# Mixer-Analog-OPA2134-Rev-K.net
KiCad netlist of a schematic drawn in EAGLE
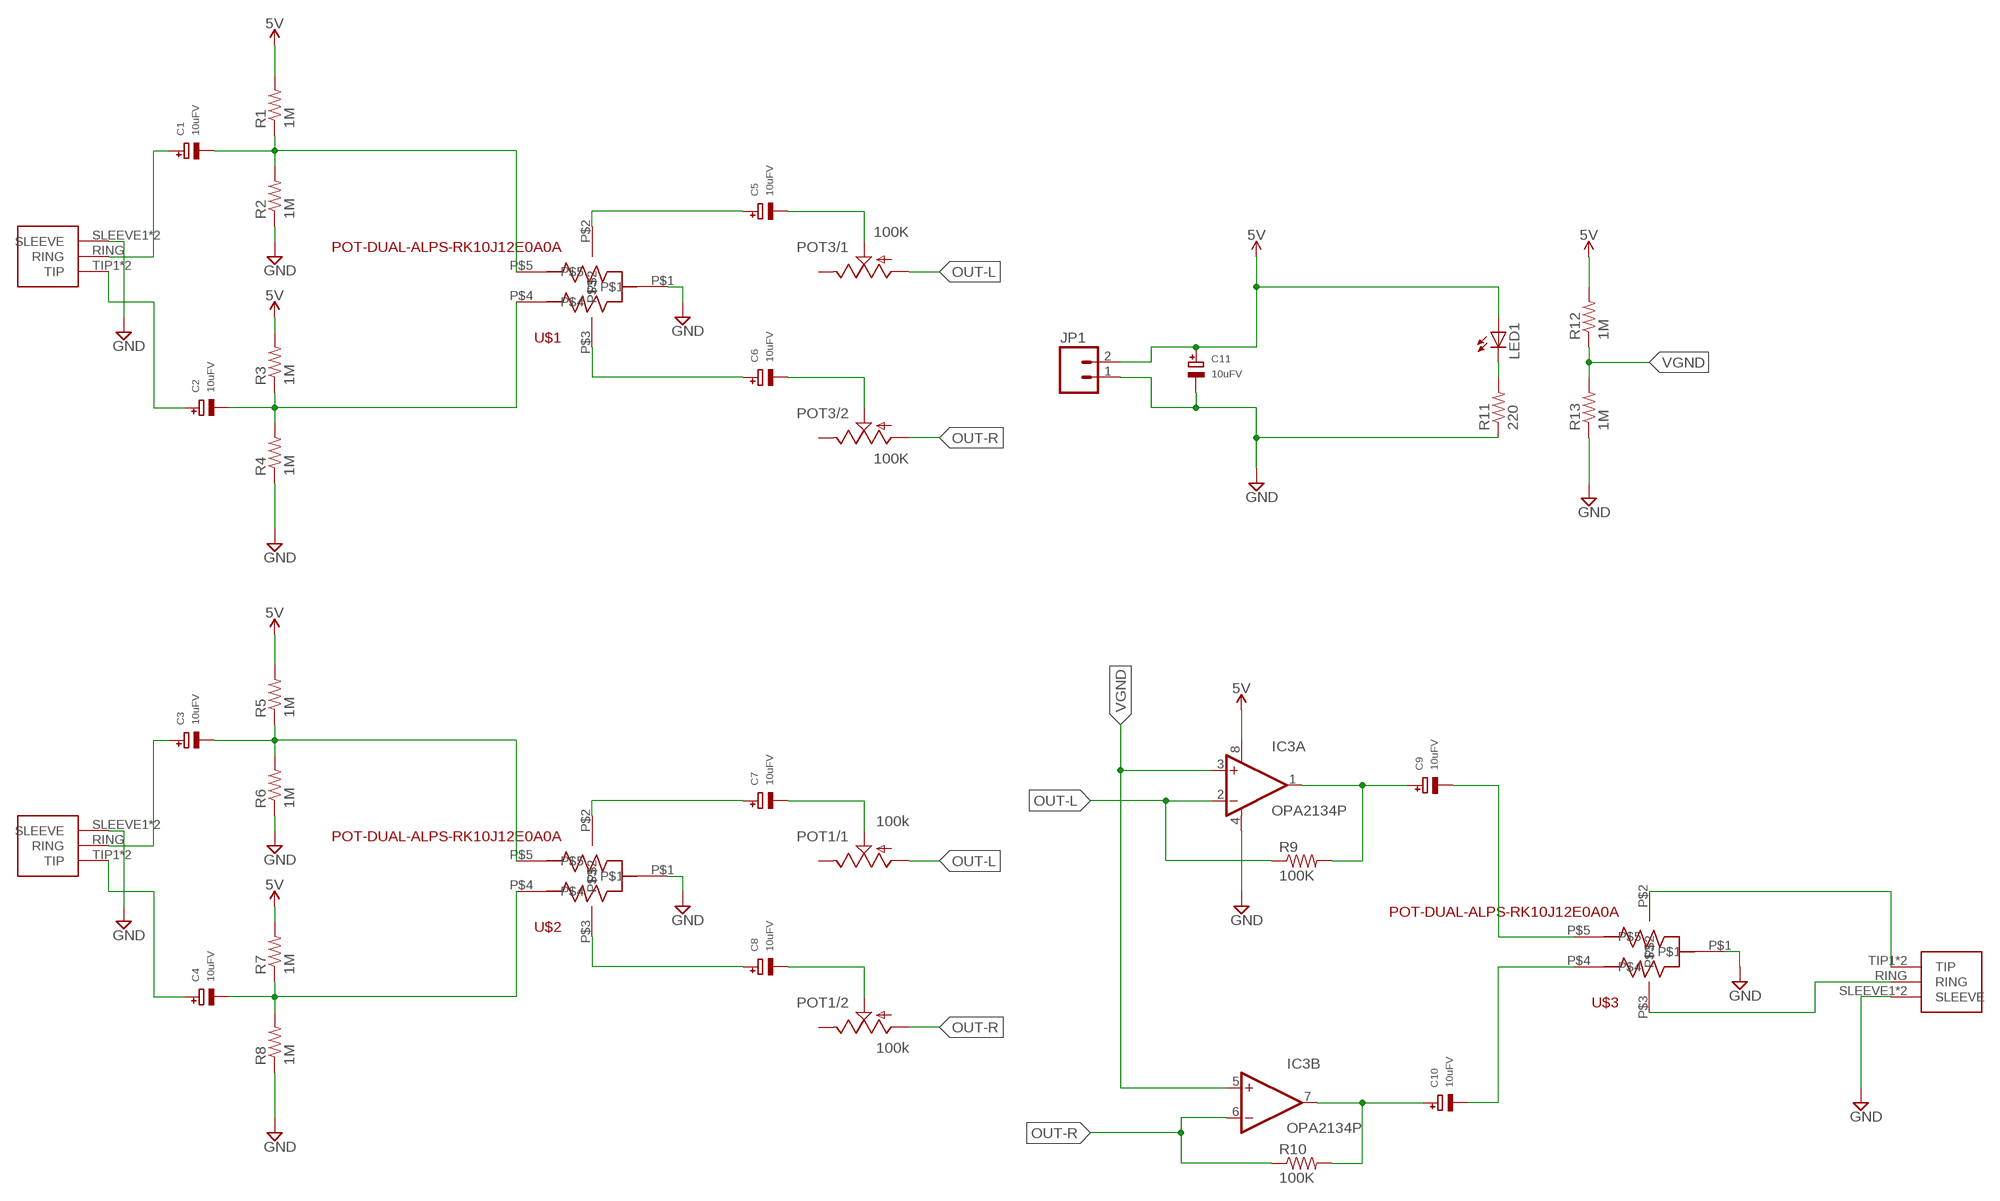
[diagram p0: schematic, sheet 1]

(export (version "E")
  (design (tool "Eeschema 10.0.6"))
  (components
    (comp (ref "C1")
      (value "10uFV")
      (footprint "eagle-import:CELEC_3.5MM_8MM")
      (libsource (lib "eagle-import") (part "CAP_ELECTROLYTICPTH_3.5MMGRID_8MMDIA"))
    )
    (comp (ref "C2")
      (value "10uFV")
      (footprint "eagle-import:CELEC_3.5MM_8MM")
      (libsource (lib "eagle-import") (part "CAP_ELECTROLYTICPTH_3.5MMGRID_8MMDIA"))
    )
    (comp (ref "C3")
      (value "10uFV")
      (footprint "eagle-import:CELEC_3.5MM_8MM")
      (libsource (lib "eagle-import") (part "CAP_ELECTROLYTICPTH_3.5MMGRID_8MMDIA"))
    )
    (comp (ref "C4")
      (value "10uFV")
      (footprint "eagle-import:CELEC_3.5MM_8MM")
      (libsource (lib "eagle-import") (part "CAP_ELECTROLYTICPTH_3.5MMGRID_8MMDIA"))
    )
    (comp (ref "C5")
      (value "10uFV")
      (footprint "eagle-import:CELEC_3.5MM_8MM")
      (libsource (lib "eagle-import") (part "CAP_ELECTROLYTICPTH_3.5MMGRID_8MMDIA"))
    )
    (comp (ref "C6")
      (value "10uFV")
      (footprint "eagle-import:CELEC_3.5MM_8MM")
      (libsource (lib "eagle-import") (part "CAP_ELECTROLYTICPTH_3.5MMGRID_8MMDIA"))
    )
    (comp (ref "C7")
      (value "10uFV")
      (footprint "eagle-import:CELEC_3.5MM_8MM")
      (libsource (lib "eagle-import") (part "CAP_ELECTROLYTICPTH_3.5MMGRID_8MMDIA"))
    )
    (comp (ref "C8")
      (value "10uFV")
      (footprint "eagle-import:CELEC_3.5MM_8MM")
      (libsource (lib "eagle-import") (part "CAP_ELECTROLYTICPTH_3.5MMGRID_8MMDIA"))
    )
    (comp (ref "C9")
      (value "10uFV")
      (footprint "eagle-import:CELEC_3.5MM_8MM")
      (libsource (lib "eagle-import") (part "CAP_ELECTROLYTICPTH_3.5MMGRID_8MMDIA"))
    )
    (comp (ref "C10")
      (value "10uFV")
      (footprint "eagle-import:CELEC_3.5MM_8MM")
      (libsource (lib "eagle-import") (part "CAP_ELECTROLYTICPTH_3.5MMGRID_8MMDIA"))
    )
    (comp (ref "C11")
      (value "10uFV")
      (footprint "eagle-import:CELEC_3.5MM_8MM")
      (libsource (lib "eagle-import") (part "CAP_ELECTROLYTICPTH_3.5MMGRID_8MMDIA"))
    )
    (comp (ref "IC3")
      (value "OPA2134P")
      (footprint "eagle-import:DIL08")
      (fields (field (name "MF") "TEXAS INSTRUMENTS") (field (name "MPN") "OPA2134PA"))
      (libsource (lib "eagle-import") (part "OPA2134P"))
    )
    (comp (ref "J1")
      (value "1/8\"-F-STEREO-PCB")
      (footprint "eagle-import:1_8_-F-STEREO-PCB")
      (libsource (lib "eagle-import") (part "1/8{dblquote}-F-STEREO-PCB"))
    )
    (comp (ref "J2")
      (value "1/8\"-F-STEREO-PCB")
      (footprint "eagle-import:1_8_-F-STEREO-PCB")
      (libsource (lib "eagle-import") (part "1/8{dblquote}-F-STEREO-PCB"))
    )
    (comp (ref "J3")
      (value "1/8\"-F-STEREO-PCB")
      (footprint "eagle-import:1_8_-F-STEREO-PCB")
      (libsource (lib "eagle-import") (part "1/8{dblquote}-F-STEREO-PCB"))
    )
    (comp (ref "JP1")
      (value "M02LOCK")
      (footprint "eagle-import:1X02_LOCK")
      (libsource (lib "eagle-import") (part "M02LOCK"))
    )
    (comp (ref "LED1")
      (value "LED3MM")
      (footprint "eagle-import:LED3MM")
      (libsource (lib "eagle-import") (part "LED3MM"))
    )
    (comp (ref "POT1")
      (value "100k")
      (footprint "eagle-import:PTV112")
      (fields
        (field (name "MF") "STMicroelectronics")
        (field (name "MP") "PTV112")
        (field (name "SPICEPREFIX") "J")
      )
      (libsource (lib "eagle-import") (part "POT-DUAL-PTV112-4420"))
    )
    (comp (ref "POT3")
      (value "100K")
      (footprint "eagle-import:PTV112")
      (fields
        (field (name "MF") "STMicroelectronics")
        (field (name "MP") "PTV112")
        (field (name "SPICEPREFIX") "J")
      )
      (libsource (lib "eagle-import") (part "POT-DUAL-PTV112-4420"))
    )
    (comp (ref "R1")
      (value "1M")
      (footprint "eagle-import:AXIAL-0.3EZ")
      (fields (field (name "SPICEPREFIX") "R"))
      (libsource (lib "eagle-import") (part "RESISTOREZ"))
    )
    (comp (ref "R2")
      (value "1M")
      (footprint "eagle-import:AXIAL-0.3")
      (fields (field (name "SPICEPREFIX") "R"))
      (libsource (lib "eagle-import") (part "RESISTORAXIAL-0.3"))
    )
    (comp (ref "R3")
      (value "1M")
      (footprint "eagle-import:AXIAL-0.3EZ")
      (fields (field (name "SPICEPREFIX") "R"))
      (libsource (lib "eagle-import") (part "RESISTOREZ"))
    )
    (comp (ref "R4")
      (value "1M")
      (footprint "eagle-import:AXIAL-0.3EZ")
      (fields (field (name "SPICEPREFIX") "R"))
      (libsource (lib "eagle-import") (part "RESISTOREZ"))
    )
    (comp (ref "R5")
      (value "1M")
      (footprint "eagle-import:AXIAL-0.3EZ")
      (fields (field (name "SPICEPREFIX") "R"))
      (libsource (lib "eagle-import") (part "RESISTOREZ"))
    )
    (comp (ref "R6")
      (value "1M")
      (footprint "eagle-import:AXIAL-0.3")
      (fields (field (name "SPICEPREFIX") "R"))
      (libsource (lib "eagle-import") (part "RESISTORAXIAL-0.3"))
    )
    (comp (ref "R7")
      (value "1M")
      (footprint "eagle-import:AXIAL-0.3EZ")
      (fields (field (name "SPICEPREFIX") "R"))
      (libsource (lib "eagle-import") (part "RESISTOREZ"))
    )
    (comp (ref "R8")
      (value "1M")
      (footprint "eagle-import:AXIAL-0.3EZ")
      (fields (field (name "SPICEPREFIX") "R"))
      (libsource (lib "eagle-import") (part "RESISTOREZ"))
    )
    (comp (ref "R9")
      (value "100K")
      (footprint "eagle-import:AXIAL-0.3EZ")
      (fields (field (name "SPICEPREFIX") "R"))
      (libsource (lib "eagle-import") (part "RESISTOREZ"))
    )
    (comp (ref "R10")
      (value "100K")
      (footprint "eagle-import:AXIAL-0.3EZ")
      (fields (field (name "SPICEPREFIX") "R"))
      (libsource (lib "eagle-import") (part "RESISTOREZ"))
    )
    (comp (ref "R11")
      (value "220")
      (footprint "eagle-import:AXIAL-0.3EZ")
      (libsource (lib "eagle-import") (part "RESISTOREZ"))
    )
    (comp (ref "R12")
      (value "1M")
      (footprint "eagle-import:AXIAL-0.3EZ")
      (libsource (lib "eagle-import") (part "RESISTOREZ"))
    )
    (comp (ref "R13")
      (value "1M")
      (footprint "eagle-import:AXIAL-0.3EZ")
      (libsource (lib "eagle-import") (part "RESISTOREZ"))
    )
    (comp (ref "U$1")
      (value "POT-DUAL-ALPS-RK10J12E0A0A")
      (footprint "eagle-import:POT-DUAL-ALPS-RK10J12E0A0A")
      (libsource (lib "eagle-import") (part "POT-DUAL-ALPS-RK10J12E0A0A"))
    )
    (comp (ref "U$2")
      (value "POT-DUAL-ALPS-RK10J12E0A0A")
      (footprint "eagle-import:POT-DUAL-ALPS-RK10J12E0A0A")
      (libsource (lib "eagle-import") (part "POT-DUAL-ALPS-RK10J12E0A0A"))
    )
    (comp (ref "U$3")
      (value "POT-DUAL-ALPS-RK10J12E0A0A")
      (footprint "eagle-import:POT-DUAL-ALPS-RK10J12E0A0A")
      (libsource (lib "eagle-import") (part "POT-DUAL-ALPS-RK10J12E0A0A"))
    )
  )
  (nets
    (net (code "1") (name "5V") (class "Default")
      (node (ref "C11") (pin "+") (pinfunction "+_+") (pintype "passive"))
      (node (ref "IC3") (pin "8") (pinfunction "V+_8") (pintype "power_in"))
      (node (ref "JP1") (pin "2") (pinfunction "2_2") (pintype "passive"))
      (node (ref "LED1") (pin "A") (pinfunction "A_A") (pintype "passive"))
      (node (ref "R1") (pin "P$2") (pinfunction "2_P$2") (pintype "passive"))
      (node (ref "R12") (pin "P$2") (pinfunction "2_P$2") (pintype "passive"))
      (node (ref "R3") (pin "P$2") (pinfunction "2_P$2") (pintype "passive"))
      (node (ref "R5") (pin "P$2") (pinfunction "2_P$2") (pintype "passive"))
      (node (ref "R7") (pin "P$2") (pinfunction "2_P$2") (pintype "passive"))
    )
    (net (code "2") (name "GND") (class "Default")
      (node (ref "C11") (pin "-") (pinfunction "-_-") (pintype "passive"))
      (node (ref "IC3") (pin "4") (pinfunction "V-_4") (pintype "power_in"))
      (node (ref "J1") (pin "SLEEVE1") (pinfunction "SLEEVE_SLEEVE1") (pintype "bidirectional"))
      (node (ref "J1") (pin "SLEEVE2") (pinfunction "SLEEVE_SLEEVE2") (pintype "bidirectional"))
      (node (ref "J2") (pin "SLEEVE1") (pinfunction "SLEEVE_SLEEVE1") (pintype "bidirectional"))
      (node (ref "J2") (pin "SLEEVE2") (pinfunction "SLEEVE_SLEEVE2") (pintype "bidirectional"))
      (node (ref "J3") (pin "SLEEVE1") (pinfunction "SLEEVE_SLEEVE1") (pintype "bidirectional"))
      (node (ref "J3") (pin "SLEEVE2") (pinfunction "SLEEVE_SLEEVE2") (pintype "bidirectional"))
      (node (ref "JP1") (pin "1") (pinfunction "1_1") (pintype "passive"))
      (node (ref "R11") (pin "P$1") (pinfunction "1_P$1") (pintype "passive"))
      (node (ref "R13") (pin "P$1") (pinfunction "1_P$1") (pintype "passive"))
      (node (ref "R2") (pin "P$1") (pinfunction "1_P$1") (pintype "passive"))
      (node (ref "R4") (pin "P$1") (pinfunction "1_P$1") (pintype "passive"))
      (node (ref "R6") (pin "P$1") (pinfunction "1_P$1") (pintype "passive"))
      (node (ref "R8") (pin "P$1") (pinfunction "1_P$1") (pintype "passive"))
      (node (ref "U$1") (pin "P$1") (pinfunction "P$1_P$1") (pintype "bidirectional"))
      (node (ref "U$2") (pin "P$1") (pinfunction "P$1_P$1") (pintype "bidirectional"))
      (node (ref "U$3") (pin "P$1") (pinfunction "P$1_P$1") (pintype "bidirectional"))
    )
    (net (code "3") (name "Net-(C1-Pad+)") (class "Default")
      (node (ref "C1") (pin "+") (pinfunction "+_+") (pintype "passive"))
      (node (ref "J1") (pin "RING") (pinfunction "RING_RING") (pintype "bidirectional"))
    )
    (net (code "4") (name "Net-(C2-Pad+)") (class "Default")
      (node (ref "C2") (pin "+") (pinfunction "+_+") (pintype "passive"))
      (node (ref "J1") (pin "TIP1") (pinfunction "TIP_TIP1") (pintype "bidirectional"))
      (node (ref "J1") (pin "TIP2") (pinfunction "TIP_TIP2") (pintype "bidirectional"))
    )
    (net (code "5") (name "Net-(C3-Pad+)") (class "Default")
      (node (ref "C3") (pin "+") (pinfunction "+_+") (pintype "passive"))
      (node (ref "J2") (pin "RING") (pinfunction "RING_RING") (pintype "bidirectional"))
    )
    (net (code "6") (name "Net-(C4-Pad+)") (class "Default")
      (node (ref "C4") (pin "+") (pinfunction "+_+") (pintype "passive"))
      (node (ref "J2") (pin "TIP1") (pinfunction "TIP_TIP1") (pintype "bidirectional"))
      (node (ref "J2") (pin "TIP2") (pinfunction "TIP_TIP2") (pintype "bidirectional"))
    )
    (net (code "7") (name "Net-(C5-Pad+)") (class "Default")
      (node (ref "C5") (pin "+") (pinfunction "+_+") (pintype "passive"))
      (node (ref "U$1") (pin "P$2") (pinfunction "P$2_P$2") (pintype "bidirectional"))
    )
    (net (code "8") (name "Net-(C6-Pad+)") (class "Default")
      (node (ref "C6") (pin "+") (pinfunction "+_+") (pintype "passive"))
      (node (ref "U$1") (pin "P$3") (pinfunction "P$3_P$3") (pintype "bidirectional"))
    )
    (net (code "9") (name "Net-(C7-Pad+)") (class "Default")
      (node (ref "C7") (pin "+") (pinfunction "+_+") (pintype "passive"))
      (node (ref "U$2") (pin "P$2") (pinfunction "P$2_P$2") (pintype "bidirectional"))
    )
    (net (code "10") (name "Net-(C8-Pad+)") (class "Default")
      (node (ref "C8") (pin "+") (pinfunction "+_+") (pintype "passive"))
      (node (ref "U$2") (pin "P$3") (pinfunction "P$3_P$3") (pintype "bidirectional"))
    )
    (net (code "11") (name "Net-(C9-Pad-)") (class "Default")
      (node (ref "C9") (pin "-") (pinfunction "-_-") (pintype "passive"))
      (node (ref "U$3") (pin "P$5") (pinfunction "P$5_P$5") (pintype "bidirectional"))
    )
    (net (code "12") (name "Net-(C10-Pad-)") (class "Default")
      (node (ref "C10") (pin "-") (pinfunction "-_-") (pintype "passive"))
      (node (ref "U$3") (pin "P$4") (pinfunction "P$4_P$4") (pintype "bidirectional"))
    )
    (net (code "13") (name "Net-(IC3A-OUT)") (class "Default")
      (node (ref "C9") (pin "+") (pinfunction "+_+") (pintype "passive"))
      (node (ref "IC3") (pin "1") (pinfunction "OUT_1") (pintype "output"))
      (node (ref "R9") (pin "P$2") (pinfunction "2_P$2") (pintype "passive"))
    )
    (net (code "14") (name "Net-(IC3B-OUT)") (class "Default")
      (node (ref "C10") (pin "+") (pinfunction "+_+") (pintype "passive"))
      (node (ref "IC3") (pin "7") (pinfunction "OUT_7") (pintype "output"))
      (node (ref "R10") (pin "P$2") (pinfunction "2_P$2") (pintype "passive"))
    )
    (net (code "15") (name "Net-(J3-PadRING)") (class "Default")
      (node (ref "J3") (pin "RING") (pinfunction "RING_RING") (pintype "bidirectional"))
      (node (ref "U$3") (pin "P$3") (pinfunction "P$3_P$3") (pintype "bidirectional"))
    )
    (net (code "16") (name "Net-(J3-TIP-PadTIP1)") (class "Default")
      (node (ref "J3") (pin "TIP1") (pinfunction "TIP_TIP1") (pintype "bidirectional"))
      (node (ref "J3") (pin "TIP2") (pinfunction "TIP_TIP2") (pintype "bidirectional"))
      (node (ref "U$3") (pin "P$2") (pinfunction "P$2_P$2") (pintype "bidirectional"))
    )
    (net (code "17") (name "Net-(LED1-C)") (class "Default")
      (node (ref "LED1") (pin "K") (pinfunction "C_K") (pintype "passive"))
      (node (ref "R11") (pin "P$2") (pinfunction "2_P$2") (pintype "passive"))
    )
    (net (code "18") (name "Net-(POT1A-S)") (class "Default")
      (node (ref "C7") (pin "-") (pinfunction "-_-") (pintype "passive"))
      (node (ref "POT1") (pin "1.2") (pinfunction "S_1.2") (pintype "passive"))
    )
    (net (code "19") (name "Net-(POT1B-S)") (class "Default")
      (node (ref "C8") (pin "-") (pinfunction "-_-") (pintype "passive"))
      (node (ref "POT1") (pin "2.2") (pinfunction "S_2.2") (pintype "passive"))
    )
    (net (code "20") (name "Net-(POT3A-S)") (class "Default")
      (node (ref "C5") (pin "-") (pinfunction "-_-") (pintype "passive"))
      (node (ref "POT3") (pin "1.2") (pinfunction "S_1.2") (pintype "passive"))
    )
    (net (code "21") (name "Net-(POT3B-S)") (class "Default")
      (node (ref "C6") (pin "-") (pinfunction "-_-") (pintype "passive"))
      (node (ref "POT3") (pin "2.2") (pinfunction "S_2.2") (pintype "passive"))
    )
    (net (code "22") (name "Net-(R1-1)") (class "Default")
      (node (ref "C1") (pin "-") (pinfunction "-_-") (pintype "passive"))
      (node (ref "R1") (pin "P$1") (pinfunction "1_P$1") (pintype "passive"))
      (node (ref "R2") (pin "P$2") (pinfunction "2_P$2") (pintype "passive"))
      (node (ref "U$1") (pin "P$5") (pinfunction "P$5_P$5") (pintype "bidirectional"))
    )
    (net (code "23") (name "Net-(R3-1)") (class "Default")
      (node (ref "C2") (pin "-") (pinfunction "-_-") (pintype "passive"))
      (node (ref "R3") (pin "P$1") (pinfunction "1_P$1") (pintype "passive"))
      (node (ref "R4") (pin "P$2") (pinfunction "2_P$2") (pintype "passive"))
      (node (ref "U$1") (pin "P$4") (pinfunction "P$4_P$4") (pintype "bidirectional"))
    )
    (net (code "24") (name "Net-(R5-1)") (class "Default")
      (node (ref "C3") (pin "-") (pinfunction "-_-") (pintype "passive"))
      (node (ref "R5") (pin "P$1") (pinfunction "1_P$1") (pintype "passive"))
      (node (ref "R6") (pin "P$2") (pinfunction "2_P$2") (pintype "passive"))
      (node (ref "U$2") (pin "P$5") (pinfunction "P$5_P$5") (pintype "bidirectional"))
    )
    (net (code "25") (name "Net-(R7-1)") (class "Default")
      (node (ref "C4") (pin "-") (pinfunction "-_-") (pintype "passive"))
      (node (ref "R7") (pin "P$1") (pinfunction "1_P$1") (pintype "passive"))
      (node (ref "R8") (pin "P$2") (pinfunction "2_P$2") (pintype "passive"))
      (node (ref "U$2") (pin "P$4") (pinfunction "P$4_P$4") (pintype "bidirectional"))
    )
    (net (code "26") (name "OUT-L") (class "Default")
      (node (ref "IC3") (pin "2") (pinfunction "-IN_2") (pintype "input"))
      (node (ref "POT1") (pin "1.1") (pinfunction "A_1.1") (pintype "passive"))
      (node (ref "POT3") (pin "1.1") (pinfunction "A_1.1") (pintype "passive"))
      (node (ref "R9") (pin "P$1") (pinfunction "1_P$1") (pintype "passive"))
    )
    (net (code "27") (name "OUT-R") (class "Default")
      (node (ref "IC3") (pin "6") (pinfunction "-IN_6") (pintype "input"))
      (node (ref "POT1") (pin "2.1") (pinfunction "A_2.1") (pintype "passive"))
      (node (ref "POT3") (pin "2.1") (pinfunction "A_2.1") (pintype "passive"))
      (node (ref "R10") (pin "P$1") (pinfunction "1_P$1") (pintype "passive"))
    )
    (net (code "28") (name "VGND") (class "Default")
      (node (ref "IC3") (pin "3") (pinfunction "+IN_3") (pintype "input"))
      (node (ref "IC3") (pin "5") (pinfunction "+IN_5") (pintype "input"))
      (node (ref "R12") (pin "P$1") (pinfunction "1_P$1") (pintype "passive"))
      (node (ref "R13") (pin "P$2") (pinfunction "2_P$2") (pintype "passive"))
    )
    (net (code "29") (name "unconnected-(POT1A-E-Pad1.3)") (class "Default")
      (node (ref "POT1") (pin "1.3") (pinfunction "E_1.3") (pintype "passive"))
    )
    (net (code "30") (name "unconnected-(POT1B-E-Pad2.3)") (class "Default")
      (node (ref "POT1") (pin "2.3") (pinfunction "E_2.3") (pintype "passive"))
    )
    (net (code "31") (name "unconnected-(POT3A-E-Pad1.3)") (class "Default")
      (node (ref "POT3") (pin "1.3") (pinfunction "E_1.3") (pintype "passive"))
    )
    (net (code "32") (name "unconnected-(POT3B-E-Pad2.3)") (class "Default")
      (node (ref "POT3") (pin "2.3") (pinfunction "E_2.3") (pintype "passive"))
    )
  )
)
